# sketch_v1_01.net
KiCad netlist of a schematic drawn in EAGLE
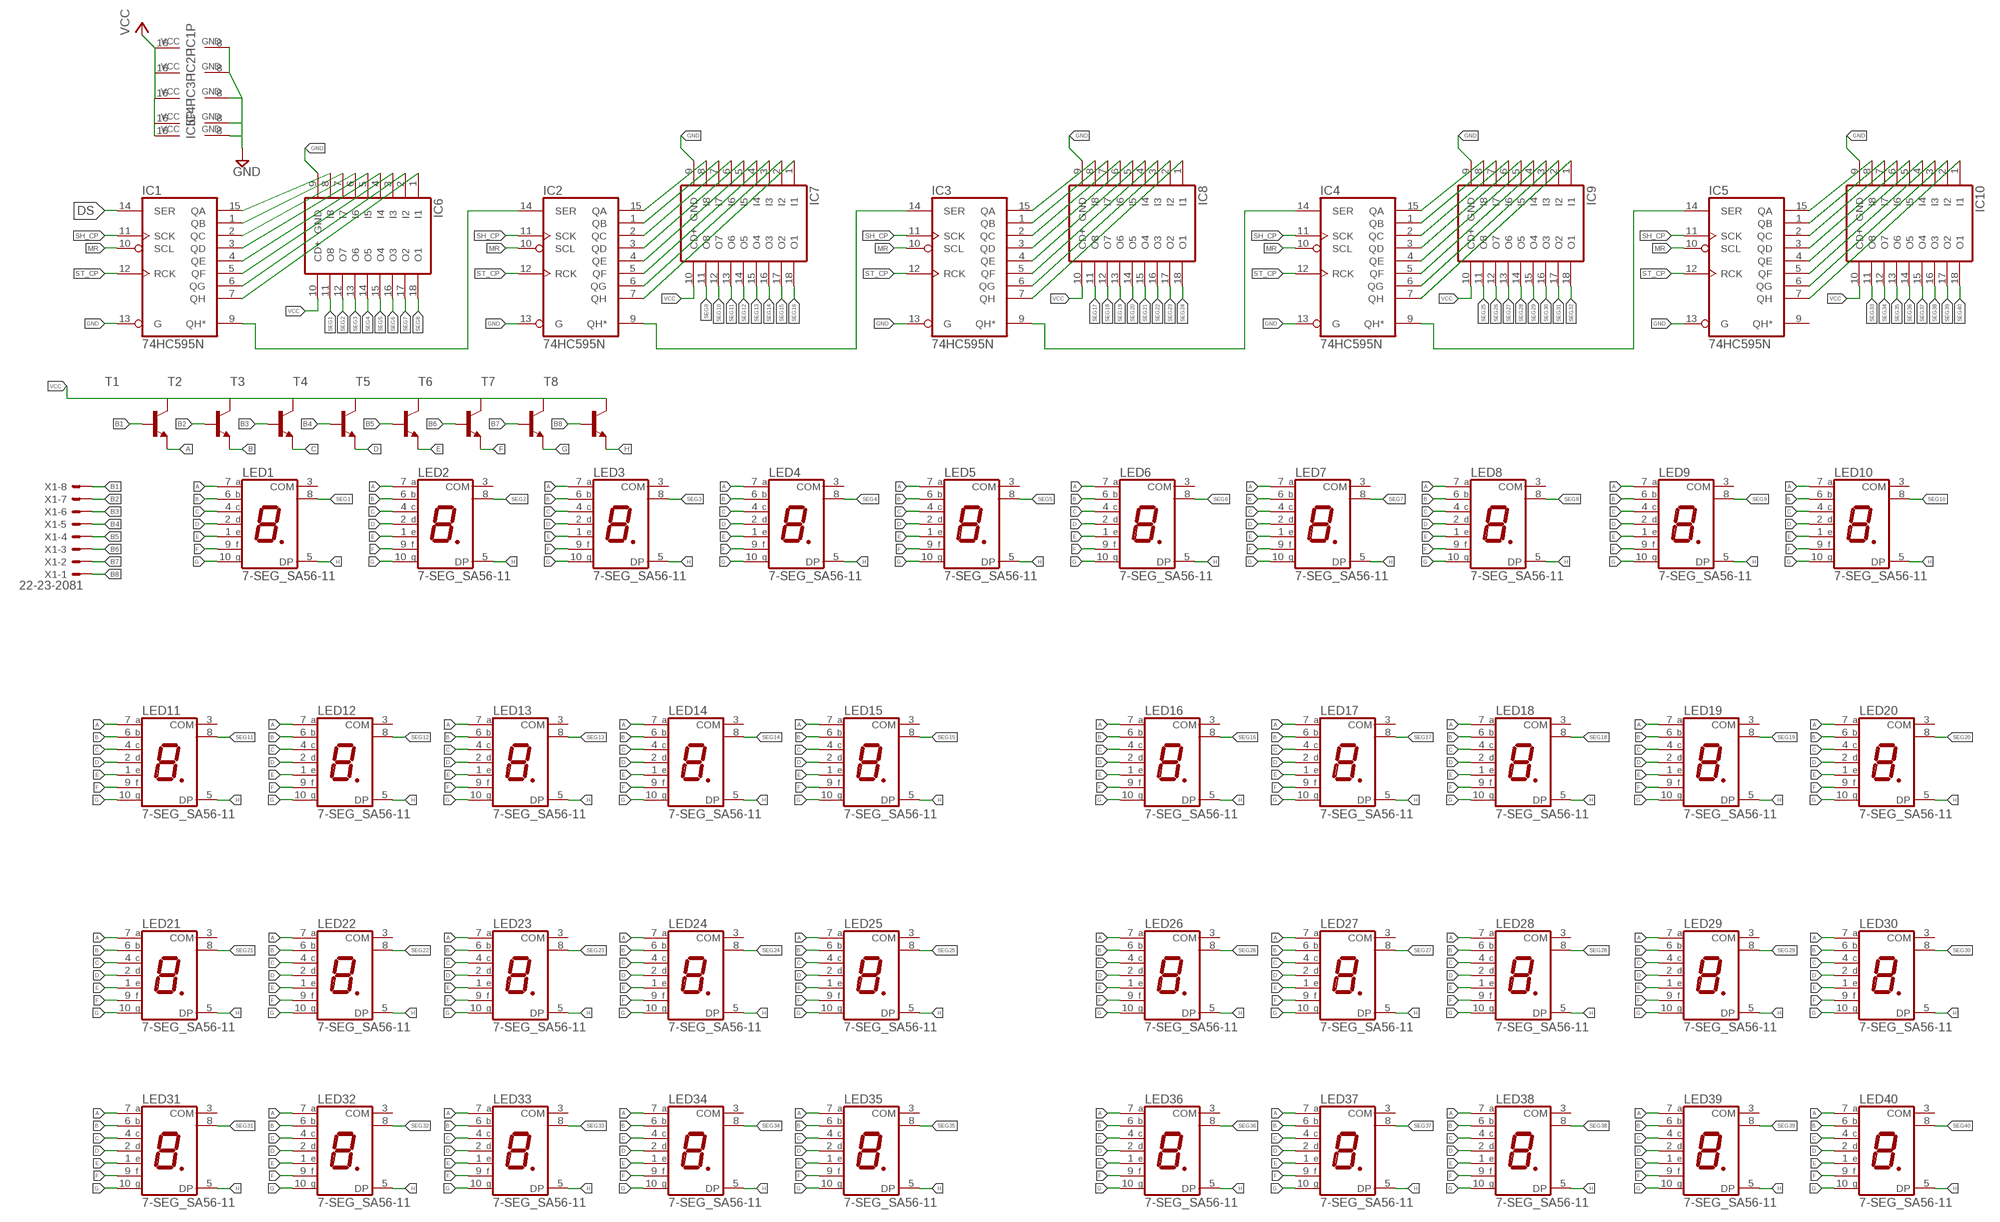
[diagram p0: schematic, sheet 1]

(export (version "E")
  (design (tool "Eeschema 10.0.6"))
  (components
    (comp (ref "IC1")
      (value "74HC595N")
      (footprint "eagle-import:DIL16")
      (libsource (lib "eagle-import") (part "74595NHC"))
    )
    (comp (ref "IC2")
      (value "74HC595N")
      (footprint "eagle-import:DIL16")
      (libsource (lib "eagle-import") (part "74595NHC"))
    )
    (comp (ref "IC3")
      (value "74HC595N")
      (footprint "eagle-import:DIL16")
      (libsource (lib "eagle-import") (part "74595NHC"))
    )
    (comp (ref "IC4")
      (value "74HC595N")
      (footprint "eagle-import:DIL16")
      (libsource (lib "eagle-import") (part "74595NHC"))
    )
    (comp (ref "IC5")
      (value "74HC595N")
      (footprint "eagle-import:DIL16")
      (libsource (lib "eagle-import") (part "74595NHC"))
    )
    (comp (ref "IC6")
      (value "ULN2803A")
      (footprint "eagle-import:DIL18")
      (libsource (lib "eagle-import") (part "ULN2803A"))
    )
    (comp (ref "IC7")
      (value "ULN2803A")
      (footprint "eagle-import:DIL18")
      (libsource (lib "eagle-import") (part "ULN2803A"))
    )
    (comp (ref "IC8")
      (value "ULN2803A")
      (footprint "eagle-import:DIL18")
      (libsource (lib "eagle-import") (part "ULN2803A"))
    )
    (comp (ref "IC9")
      (value "ULN2803A")
      (footprint "eagle-import:DIL18")
      (libsource (lib "eagle-import") (part "ULN2803A"))
    )
    (comp (ref "IC10")
      (value "ULN2803A")
      (footprint "eagle-import:DIL18")
      (libsource (lib "eagle-import") (part "ULN2803A"))
    )
    (comp (ref "LED1")
      (value "7-SEG_SA56-11")
      (footprint "eagle-import:SA56-11")
      (libsource (lib "eagle-import") (part "7-SEG_SA56-11"))
    )
    (comp (ref "LED2")
      (value "7-SEG_SA56-11")
      (footprint "eagle-import:SA56-11")
      (libsource (lib "eagle-import") (part "7-SEG_SA56-11"))
    )
    (comp (ref "LED3")
      (value "7-SEG_SA56-11")
      (footprint "eagle-import:SA56-11")
      (libsource (lib "eagle-import") (part "7-SEG_SA56-11"))
    )
    (comp (ref "LED4")
      (value "7-SEG_SA56-11")
      (footprint "eagle-import:SA56-11")
      (libsource (lib "eagle-import") (part "7-SEG_SA56-11"))
    )
    (comp (ref "LED5")
      (value "7-SEG_SA56-11")
      (footprint "eagle-import:SA56-11")
      (libsource (lib "eagle-import") (part "7-SEG_SA56-11"))
    )
    (comp (ref "LED6")
      (value "7-SEG_SA56-11")
      (footprint "eagle-import:SA56-11")
      (libsource (lib "eagle-import") (part "7-SEG_SA56-11"))
    )
    (comp (ref "LED7")
      (value "7-SEG_SA56-11")
      (footprint "eagle-import:SA56-11")
      (libsource (lib "eagle-import") (part "7-SEG_SA56-11"))
    )
    (comp (ref "LED8")
      (value "7-SEG_SA56-11")
      (footprint "eagle-import:SA56-11")
      (libsource (lib "eagle-import") (part "7-SEG_SA56-11"))
    )
    (comp (ref "LED9")
      (value "7-SEG_SA56-11")
      (footprint "eagle-import:SA56-11")
      (libsource (lib "eagle-import") (part "7-SEG_SA56-11"))
    )
    (comp (ref "LED10")
      (value "7-SEG_SA56-11")
      (footprint "eagle-import:SA56-11")
      (libsource (lib "eagle-import") (part "7-SEG_SA56-11"))
    )
    (comp (ref "LED11")
      (value "7-SEG_SA56-11")
      (footprint "eagle-import:SA56-11")
      (libsource (lib "eagle-import") (part "7-SEG_SA56-11"))
    )
    (comp (ref "LED12")
      (value "7-SEG_SA56-11")
      (footprint "eagle-import:SA56-11")
      (libsource (lib "eagle-import") (part "7-SEG_SA56-11"))
    )
    (comp (ref "LED13")
      (value "7-SEG_SA56-11")
      (footprint "eagle-import:SA56-11")
      (libsource (lib "eagle-import") (part "7-SEG_SA56-11"))
    )
    (comp (ref "LED14")
      (value "7-SEG_SA56-11")
      (footprint "eagle-import:SA56-11")
      (libsource (lib "eagle-import") (part "7-SEG_SA56-11"))
    )
    (comp (ref "LED15")
      (value "7-SEG_SA56-11")
      (footprint "eagle-import:SA56-11")
      (libsource (lib "eagle-import") (part "7-SEG_SA56-11"))
    )
    (comp (ref "LED16")
      (value "7-SEG_SA56-11")
      (footprint "eagle-import:SA56-11")
      (libsource (lib "eagle-import") (part "7-SEG_SA56-11"))
    )
    (comp (ref "LED17")
      (value "7-SEG_SA56-11")
      (footprint "eagle-import:SA56-11")
      (libsource (lib "eagle-import") (part "7-SEG_SA56-11"))
    )
    (comp (ref "LED18")
      (value "7-SEG_SA56-11")
      (footprint "eagle-import:SA56-11")
      (libsource (lib "eagle-import") (part "7-SEG_SA56-11"))
    )
    (comp (ref "LED19")
      (value "7-SEG_SA56-11")
      (footprint "eagle-import:SA56-11")
      (libsource (lib "eagle-import") (part "7-SEG_SA56-11"))
    )
    (comp (ref "LED20")
      (value "7-SEG_SA56-11")
      (footprint "eagle-import:SA56-11")
      (libsource (lib "eagle-import") (part "7-SEG_SA56-11"))
    )
    (comp (ref "LED21")
      (value "7-SEG_SA56-11")
      (footprint "eagle-import:SA56-11")
      (libsource (lib "eagle-import") (part "7-SEG_SA56-11"))
    )
    (comp (ref "LED22")
      (value "7-SEG_SA56-11")
      (footprint "eagle-import:SA56-11")
      (libsource (lib "eagle-import") (part "7-SEG_SA56-11"))
    )
    (comp (ref "LED23")
      (value "7-SEG_SA56-11")
      (footprint "eagle-import:SA56-11")
      (libsource (lib "eagle-import") (part "7-SEG_SA56-11"))
    )
    (comp (ref "LED24")
      (value "7-SEG_SA56-11")
      (footprint "eagle-import:SA56-11")
      (libsource (lib "eagle-import") (part "7-SEG_SA56-11"))
    )
    (comp (ref "LED25")
      (value "7-SEG_SA56-11")
      (footprint "eagle-import:SA56-11")
      (libsource (lib "eagle-import") (part "7-SEG_SA56-11"))
    )
    (comp (ref "LED26")
      (value "7-SEG_SA56-11")
      (footprint "eagle-import:SA56-11")
      (libsource (lib "eagle-import") (part "7-SEG_SA56-11"))
    )
    (comp (ref "LED27")
      (value "7-SEG_SA56-11")
      (footprint "eagle-import:SA56-11")
      (libsource (lib "eagle-import") (part "7-SEG_SA56-11"))
    )
    (comp (ref "LED28")
      (value "7-SEG_SA56-11")
      (footprint "eagle-import:SA56-11")
      (libsource (lib "eagle-import") (part "7-SEG_SA56-11"))
    )
    (comp (ref "LED29")
      (value "7-SEG_SA56-11")
      (footprint "eagle-import:SA56-11")
      (libsource (lib "eagle-import") (part "7-SEG_SA56-11"))
    )
    (comp (ref "LED30")
      (value "7-SEG_SA56-11")
      (footprint "eagle-import:SA56-11")
      (libsource (lib "eagle-import") (part "7-SEG_SA56-11"))
    )
    (comp (ref "LED31")
      (value "7-SEG_SA56-11")
      (footprint "eagle-import:SA56-11")
      (libsource (lib "eagle-import") (part "7-SEG_SA56-11"))
    )
    (comp (ref "LED32")
      (value "7-SEG_SA56-11")
      (footprint "eagle-import:SA56-11")
      (libsource (lib "eagle-import") (part "7-SEG_SA56-11"))
    )
    (comp (ref "LED33")
      (value "7-SEG_SA56-11")
      (footprint "eagle-import:SA56-11")
      (libsource (lib "eagle-import") (part "7-SEG_SA56-11"))
    )
    (comp (ref "LED34")
      (value "7-SEG_SA56-11")
      (footprint "eagle-import:SA56-11")
      (libsource (lib "eagle-import") (part "7-SEG_SA56-11"))
    )
    (comp (ref "LED35")
      (value "7-SEG_SA56-11")
      (footprint "eagle-import:SA56-11")
      (libsource (lib "eagle-import") (part "7-SEG_SA56-11"))
    )
    (comp (ref "LED36")
      (value "7-SEG_SA56-11")
      (footprint "eagle-import:SA56-11")
      (libsource (lib "eagle-import") (part "7-SEG_SA56-11"))
    )
    (comp (ref "LED37")
      (value "7-SEG_SA56-11")
      (footprint "eagle-import:SA56-11")
      (libsource (lib "eagle-import") (part "7-SEG_SA56-11"))
    )
    (comp (ref "LED38")
      (value "7-SEG_SA56-11")
      (footprint "eagle-import:SA56-11")
      (libsource (lib "eagle-import") (part "7-SEG_SA56-11"))
    )
    (comp (ref "LED39")
      (value "7-SEG_SA56-11")
      (footprint "eagle-import:SA56-11")
      (libsource (lib "eagle-import") (part "7-SEG_SA56-11"))
    )
    (comp (ref "LED40")
      (value "7-SEG_SA56-11")
      (footprint "eagle-import:SA56-11")
      (libsource (lib "eagle-import") (part "7-SEG_SA56-11"))
    )
    (comp (ref "T1")
      (value "-NPN-TO92")
      (footprint "eagle-import:TO92")
      (libsource (lib "eagle-import") (part "-NPN-TO92"))
    )
    (comp (ref "T2")
      (value "-NPN-TO92")
      (footprint "eagle-import:TO92")
      (libsource (lib "eagle-import") (part "-NPN-TO92"))
    )
    (comp (ref "T3")
      (value "-NPN-TO92")
      (footprint "eagle-import:TO92")
      (libsource (lib "eagle-import") (part "-NPN-TO92"))
    )
    (comp (ref "T4")
      (value "-NPN-TO92")
      (footprint "eagle-import:TO92")
      (libsource (lib "eagle-import") (part "-NPN-TO92"))
    )
    (comp (ref "T5")
      (value "-NPN-TO92")
      (footprint "eagle-import:TO92")
      (libsource (lib "eagle-import") (part "-NPN-TO92"))
    )
    (comp (ref "T6")
      (value "-NPN-TO92")
      (footprint "eagle-import:TO92")
      (libsource (lib "eagle-import") (part "-NPN-TO92"))
    )
    (comp (ref "T7")
      (value "-NPN-TO92")
      (footprint "eagle-import:TO92")
      (libsource (lib "eagle-import") (part "-NPN-TO92"))
    )
    (comp (ref "T8")
      (value "-NPN-TO92")
      (footprint "eagle-import:TO92")
      (libsource (lib "eagle-import") (part "-NPN-TO92"))
    )
    (comp (ref "X1")
      (value "22-23-2081")
      (footprint "eagle-import:22-23-2081")
      (fields (field (name "MF") "MOLEX"))
      (libsource (lib "eagle-import") (part "22-23-2081"))
    )
  )
  (nets
    (net (code "1") (name "A") (class "Default")
      (node (ref "LED1") (pin "7") (pinfunction "A_7") (pintype "passive"))
      (node (ref "LED10") (pin "7") (pinfunction "A_7") (pintype "passive"))
      (node (ref "LED11") (pin "7") (pinfunction "A_7") (pintype "passive"))
      (node (ref "LED12") (pin "7") (pinfunction "A_7") (pintype "passive"))
      (node (ref "LED13") (pin "7") (pinfunction "A_7") (pintype "passive"))
      (node (ref "LED14") (pin "7") (pinfunction "A_7") (pintype "passive"))
      (node (ref "LED15") (pin "7") (pinfunction "A_7") (pintype "passive"))
      (node (ref "LED16") (pin "7") (pinfunction "A_7") (pintype "passive"))
      (node (ref "LED17") (pin "7") (pinfunction "A_7") (pintype "passive"))
      (node (ref "LED18") (pin "7") (pinfunction "A_7") (pintype "passive"))
      (node (ref "LED19") (pin "7") (pinfunction "A_7") (pintype "passive"))
      (node (ref "LED2") (pin "7") (pinfunction "A_7") (pintype "passive"))
      (node (ref "LED20") (pin "7") (pinfunction "A_7") (pintype "passive"))
      (node (ref "LED21") (pin "7") (pinfunction "A_7") (pintype "passive"))
      (node (ref "LED22") (pin "7") (pinfunction "A_7") (pintype "passive"))
      (node (ref "LED23") (pin "7") (pinfunction "A_7") (pintype "passive"))
      (node (ref "LED24") (pin "7") (pinfunction "A_7") (pintype "passive"))
      (node (ref "LED25") (pin "7") (pinfunction "A_7") (pintype "passive"))
      (node (ref "LED26") (pin "7") (pinfunction "A_7") (pintype "passive"))
      (node (ref "LED27") (pin "7") (pinfunction "A_7") (pintype "passive"))
      (node (ref "LED28") (pin "7") (pinfunction "A_7") (pintype "passive"))
      (node (ref "LED29") (pin "7") (pinfunction "A_7") (pintype "passive"))
      (node (ref "LED3") (pin "7") (pinfunction "A_7") (pintype "passive"))
      (node (ref "LED30") (pin "7") (pinfunction "A_7") (pintype "passive"))
      (node (ref "LED31") (pin "7") (pinfunction "A_7") (pintype "passive"))
      (node (ref "LED32") (pin "7") (pinfunction "A_7") (pintype "passive"))
      (node (ref "LED33") (pin "7") (pinfunction "A_7") (pintype "passive"))
      (node (ref "LED34") (pin "7") (pinfunction "A_7") (pintype "passive"))
      (node (ref "LED35") (pin "7") (pinfunction "A_7") (pintype "passive"))
      (node (ref "LED36") (pin "7") (pinfunction "A_7") (pintype "passive"))
      (node (ref "LED37") (pin "7") (pinfunction "A_7") (pintype "passive"))
      (node (ref "LED38") (pin "7") (pinfunction "A_7") (pintype "passive"))
      (node (ref "LED39") (pin "7") (pinfunction "A_7") (pintype "passive"))
      (node (ref "LED4") (pin "7") (pinfunction "A_7") (pintype "passive"))
      (node (ref "LED40") (pin "7") (pinfunction "A_7") (pintype "passive"))
      (node (ref "LED5") (pin "7") (pinfunction "A_7") (pintype "passive"))
      (node (ref "LED6") (pin "7") (pinfunction "A_7") (pintype "passive"))
      (node (ref "LED7") (pin "7") (pinfunction "A_7") (pintype "passive"))
      (node (ref "LED8") (pin "7") (pinfunction "A_7") (pintype "passive"))
      (node (ref "LED9") (pin "7") (pinfunction "A_7") (pintype "passive"))
      (node (ref "T1") (pin "1") (pinfunction "E_1") (pintype "passive"))
    )
    (net (code "2") (name "B") (class "Default")
      (node (ref "LED1") (pin "6") (pinfunction "B_6") (pintype "passive"))
      (node (ref "LED10") (pin "6") (pinfunction "B_6") (pintype "passive"))
      (node (ref "LED11") (pin "6") (pinfunction "B_6") (pintype "passive"))
      (node (ref "LED12") (pin "6") (pinfunction "B_6") (pintype "passive"))
      (node (ref "LED13") (pin "6") (pinfunction "B_6") (pintype "passive"))
      (node (ref "LED14") (pin "6") (pinfunction "B_6") (pintype "passive"))
      (node (ref "LED15") (pin "6") (pinfunction "B_6") (pintype "passive"))
      (node (ref "LED16") (pin "6") (pinfunction "B_6") (pintype "passive"))
      (node (ref "LED17") (pin "6") (pinfunction "B_6") (pintype "passive"))
      (node (ref "LED18") (pin "6") (pinfunction "B_6") (pintype "passive"))
      (node (ref "LED19") (pin "6") (pinfunction "B_6") (pintype "passive"))
      (node (ref "LED2") (pin "6") (pinfunction "B_6") (pintype "passive"))
      (node (ref "LED20") (pin "6") (pinfunction "B_6") (pintype "passive"))
      (node (ref "LED21") (pin "6") (pinfunction "B_6") (pintype "passive"))
      (node (ref "LED22") (pin "6") (pinfunction "B_6") (pintype "passive"))
      (node (ref "LED23") (pin "6") (pinfunction "B_6") (pintype "passive"))
      (node (ref "LED24") (pin "6") (pinfunction "B_6") (pintype "passive"))
      (node (ref "LED25") (pin "6") (pinfunction "B_6") (pintype "passive"))
      (node (ref "LED26") (pin "6") (pinfunction "B_6") (pintype "passive"))
      (node (ref "LED27") (pin "6") (pinfunction "B_6") (pintype "passive"))
      (node (ref "LED28") (pin "6") (pinfunction "B_6") (pintype "passive"))
      (node (ref "LED29") (pin "6") (pinfunction "B_6") (pintype "passive"))
      (node (ref "LED3") (pin "6") (pinfunction "B_6") (pintype "passive"))
      (node (ref "LED30") (pin "6") (pinfunction "B_6") (pintype "passive"))
      (node (ref "LED31") (pin "6") (pinfunction "B_6") (pintype "passive"))
      (node (ref "LED32") (pin "6") (pinfunction "B_6") (pintype "passive"))
      (node (ref "LED33") (pin "6") (pinfunction "B_6") (pintype "passive"))
      (node (ref "LED34") (pin "6") (pinfunction "B_6") (pintype "passive"))
      (node (ref "LED35") (pin "6") (pinfunction "B_6") (pintype "passive"))
      (node (ref "LED36") (pin "6") (pinfunction "B_6") (pintype "passive"))
      (node (ref "LED37") (pin "6") (pinfunction "B_6") (pintype "passive"))
      (node (ref "LED38") (pin "6") (pinfunction "B_6") (pintype "passive"))
      (node (ref "LED39") (pin "6") (pinfunction "B_6") (pintype "passive"))
      (node (ref "LED4") (pin "6") (pinfunction "B_6") (pintype "passive"))
      (node (ref "LED40") (pin "6") (pinfunction "B_6") (pintype "passive"))
      (node (ref "LED5") (pin "6") (pinfunction "B_6") (pintype "passive"))
      (node (ref "LED6") (pin "6") (pinfunction "B_6") (pintype "passive"))
      (node (ref "LED7") (pin "6") (pinfunction "B_6") (pintype "passive"))
      (node (ref "LED8") (pin "6") (pinfunction "B_6") (pintype "passive"))
      (node (ref "LED9") (pin "6") (pinfunction "B_6") (pintype "passive"))
      (node (ref "T2") (pin "1") (pinfunction "E_1") (pintype "passive"))
    )
    (net (code "3") (name "B1") (class "Default")
      (node (ref "T1") (pin "2") (pinfunction "B_2") (pintype "passive"))
      (node (ref "X1") (pin "8") (pinfunction "S_8") (pintype "passive"))
    )
    (net (code "4") (name "B2") (class "Default")
      (node (ref "T2") (pin "2") (pinfunction "B_2") (pintype "passive"))
      (node (ref "X1") (pin "7") (pinfunction "S_7") (pintype "passive"))
    )
    (net (code "5") (name "B3") (class "Default")
      (node (ref "T3") (pin "2") (pinfunction "B_2") (pintype "passive"))
      (node (ref "X1") (pin "6") (pinfunction "S_6") (pintype "passive"))
    )
    (net (code "6") (name "B4") (class "Default")
      (node (ref "T4") (pin "2") (pinfunction "B_2") (pintype "passive"))
      (node (ref "X1") (pin "5") (pinfunction "S_5") (pintype "passive"))
    )
    (net (code "7") (name "B5") (class "Default")
      (node (ref "T5") (pin "2") (pinfunction "B_2") (pintype "passive"))
      (node (ref "X1") (pin "4") (pinfunction "S_4") (pintype "passive"))
    )
    (net (code "8") (name "B6") (class "Default")
      (node (ref "T6") (pin "2") (pinfunction "B_2") (pintype "passive"))
      (node (ref "X1") (pin "3") (pinfunction "S_3") (pintype "passive"))
    )
    (net (code "9") (name "B7") (class "Default")
      (node (ref "T7") (pin "2") (pinfunction "B_2") (pintype "passive"))
      (node (ref "X1") (pin "2") (pinfunction "S_2") (pintype "passive"))
    )
    (net (code "10") (name "B8") (class "Default")
      (node (ref "T8") (pin "2") (pinfunction "B_2") (pintype "passive"))
      (node (ref "X1") (pin "1") (pinfunction "S_1") (pintype "passive"))
    )
    (net (code "11") (name "C") (class "Default")
      (node (ref "LED1") (pin "4") (pinfunction "C_4") (pintype "passive"))
      (node (ref "LED10") (pin "4") (pinfunction "C_4") (pintype "passive"))
      (node (ref "LED11") (pin "4") (pinfunction "C_4") (pintype "passive"))
      (node (ref "LED12") (pin "4") (pinfunction "C_4") (pintype "passive"))
      (node (ref "LED13") (pin "4") (pinfunction "C_4") (pintype "passive"))
      (node (ref "LED14") (pin "4") (pinfunction "C_4") (pintype "passive"))
      (node (ref "LED15") (pin "4") (pinfunction "C_4") (pintype "passive"))
      (node (ref "LED16") (pin "4") (pinfunction "C_4") (pintype "passive"))
      (node (ref "LED17") (pin "4") (pinfunction "C_4") (pintype "passive"))
      (node (ref "LED18") (pin "4") (pinfunction "C_4") (pintype "passive"))
      (node (ref "LED19") (pin "4") (pinfunction "C_4") (pintype "passive"))
      (node (ref "LED2") (pin "4") (pinfunction "C_4") (pintype "passive"))
      (node (ref "LED20") (pin "4") (pinfunction "C_4") (pintype "passive"))
      (node (ref "LED21") (pin "4") (pinfunction "C_4") (pintype "passive"))
      (node (ref "LED22") (pin "4") (pinfunction "C_4") (pintype "passive"))
      (node (ref "LED23") (pin "4") (pinfunction "C_4") (pintype "passive"))
      (node (ref "LED24") (pin "4") (pinfunction "C_4") (pintype "passive"))
      (node (ref "LED25") (pin "4") (pinfunction "C_4") (pintype "passive"))
      (node (ref "LED26") (pin "4") (pinfunction "C_4") (pintype "passive"))
      (node (ref "LED27") (pin "4") (pinfunction "C_4") (pintype "passive"))
      (node (ref "LED28") (pin "4") (pinfunction "C_4") (pintype "passive"))
      (node (ref "LED29") (pin "4") (pinfunction "C_4") (pintype "passive"))
      (node (ref "LED3") (pin "4") (pinfunction "C_4") (pintype "passive"))
      (node (ref "LED30") (pin "4") (pinfunction "C_4") (pintype "passive"))
      (node (ref "LED31") (pin "4") (pinfunction "C_4") (pintype "passive"))
      (node (ref "LED32") (pin "4") (pinfunction "C_4") (pintype "passive"))
      (node (ref "LED33") (pin "4") (pinfunction "C_4") (pintype "passive"))
      (node (ref "LED34") (pin "4") (pinfunction "C_4") (pintype "passive"))
      (node (ref "LED35") (pin "4") (pinfunction "C_4") (pintype "passive"))
      (node (ref "LED36") (pin "4") (pinfunction "C_4") (pintype "passive"))
      (node (ref "LED37") (pin "4") (pinfunction "C_4") (pintype "passive"))
      (node (ref "LED38") (pin "4") (pinfunction "C_4") (pintype "passive"))
      (node (ref "LED39") (pin "4") (pinfunction "C_4") (pintype "passive"))
      (node (ref "LED4") (pin "4") (pinfunction "C_4") (pintype "passive"))
      (node (ref "LED40") (pin "4") (pinfunction "C_4") (pintype "passive"))
      (node (ref "LED5") (pin "4") (pinfunction "C_4") (pintype "passive"))
      (node (ref "LED6") (pin "4") (pinfunction "C_4") (pintype "passive"))
      (node (ref "LED7") (pin "4") (pinfunction "C_4") (pintype "passive"))
      (node (ref "LED8") (pin "4") (pinfunction "C_4") (pintype "passive"))
      (node (ref "LED9") (pin "4") (pinfunction "C_4") (pintype "passive"))
      (node (ref "T3") (pin "1") (pinfunction "E_1") (pintype "passive"))
    )
    (net (code "12") (name "D") (class "Default")
      (node (ref "LED1") (pin "2") (pinfunction "D_2") (pintype "passive"))
      (node (ref "LED10") (pin "2") (pinfunction "D_2") (pintype "passive"))
      (node (ref "LED11") (pin "2") (pinfunction "D_2") (pintype "passive"))
      (node (ref "LED12") (pin "2") (pinfunction "D_2") (pintype "passive"))
      (node (ref "LED13") (pin "2") (pinfunction "D_2") (pintype "passive"))
      (node (ref "LED14") (pin "2") (pinfunction "D_2") (pintype "passive"))
      (node (ref "LED15") (pin "2") (pinfunction "D_2") (pintype "passive"))
      (node (ref "LED16") (pin "2") (pinfunction "D_2") (pintype "passive"))
      (node (ref "LED17") (pin "2") (pinfunction "D_2") (pintype "passive"))
      (node (ref "LED18") (pin "2") (pinfunction "D_2") (pintype "passive"))
      (node (ref "LED19") (pin "2") (pinfunction "D_2") (pintype "passive"))
      (node (ref "LED2") (pin "2") (pinfunction "D_2") (pintype "passive"))
      (node (ref "LED20") (pin "2") (pinfunction "D_2") (pintype "passive"))
      (node (ref "LED21") (pin "2") (pinfunction "D_2") (pintype "passive"))
      (node (ref "LED22") (pin "2") (pinfunction "D_2") (pintype "passive"))
      (node (ref "LED23") (pin "2") (pinfunction "D_2") (pintype "passive"))
      (node (ref "LED24") (pin "2") (pinfunction "D_2") (pintype "passive"))
      (node (ref "LED25") (pin "2") (pinfunction "D_2") (pintype "passive"))
      (node (ref "LED26") (pin "2") (pinfunction "D_2") (pintype "passive"))
      (node (ref "LED27") (pin "2") (pinfunction "D_2") (pintype "passive"))
      (node (ref "LED28") (pin "2") (pinfunction "D_2") (pintype "passive"))
      (node (ref "LED29") (pin "2") (pinfunction "D_2") (pintype "passive"))
      (node (ref "LED3") (pin "2") (pinfunction "D_2") (pintype "passive"))
      (node (ref "LED30") (pin "2") (pinfunction "D_2") (pintype "passive"))
      (node (ref "LED31") (pin "2") (pinfunction "D_2") (pintype "passive"))
      (node (ref "LED32") (pin "2") (pinfunction "D_2") (pintype "passive"))
      (node (ref "LED33") (pin "2") (pinfunction "D_2") (pintype "passive"))
      (node (ref "LED34") (pin "2") (pinfunction "D_2") (pintype "passive"))
      (node (ref "LED35") (pin "2") (pinfunction "D_2") (pintype "passive"))
      (node (ref "LED36") (pin "2") (pinfunction "D_2") (pintype "passive"))
      (node (ref "LED37") (pin "2") (pinfunction "D_2") (pintype "passive"))
      (node (ref "LED38") (pin "2") (pinfunction "D_2") (pintype "passive"))
      (node (ref "LED39") (pin "2") (pinfunction "D_2") (pintype "passive"))
      (node (ref "LED4") (pin "2") (pinfunction "D_2") (pintype "passive"))
      (node (ref "LED40") (pin "2") (pinfunction "D_2") (pintype "passive"))
      (node (ref "LED5") (pin "2") (pinfunction "D_2") (pintype "passive"))
      (node (ref "LED6") (pin "2") (pinfunction "D_2") (pintype "passive"))
      (node (ref "LED7") (pin "2") (pinfunction "D_2") (pintype "passive"))
      (node (ref "LED8") (pin "2") (pinfunction "D_2") (pintype "passive"))
      (node (ref "LED9") (pin "2") (pinfunction "D_2") (pintype "passive"))
      (node (ref "T4") (pin "1") (pinfunction "E_1") (pintype "passive"))
    )
    (net (code "13") (name "DS") (class "Default")
      (node (ref "IC1") (pin "14") (pinfunction "SER_14") (pintype "input"))
    )
    (net (code "14") (name "E") (class "Default")
      (node (ref "LED1") (pin "1") (pinfunction "E_1") (pintype "passive"))
      (node (ref "LED10") (pin "1") (pinfunction "E_1") (pintype "passive"))
      (node (ref "LED11") (pin "1") (pinfunction "E_1") (pintype "passive"))
      (node (ref "LED12") (pin "1") (pinfunction "E_1") (pintype "passive"))
      (node (ref "LED13") (pin "1") (pinfunction "E_1") (pintype "passive"))
      (node (ref "LED14") (pin "1") (pinfunction "E_1") (pintype "passive"))
      (node (ref "LED15") (pin "1") (pinfunction "E_1") (pintype "passive"))
      (node (ref "LED16") (pin "1") (pinfunction "E_1") (pintype "passive"))
      (node (ref "LED17") (pin "1") (pinfunction "E_1") (pintype "passive"))
      (node (ref "LED18") (pin "1") (pinfunction "E_1") (pintype "passive"))
      (node (ref "LED19") (pin "1") (pinfunction "E_1") (pintype "passive"))
      (node (ref "LED2") (pin "1") (pinfunction "E_1") (pintype "passive"))
      (node (ref "LED20") (pin "1") (pinfunction "E_1") (pintype "passive"))
      (node (ref "LED21") (pin "1") (pinfunction "E_1") (pintype "passive"))
      (node (ref "LED22") (pin "1") (pinfunction "E_1") (pintype "passive"))
      (node (ref "LED23") (pin "1") (pinfunction "E_1") (pintype "passive"))
      (node (ref "LED24") (pin "1") (pinfunction "E_1") (pintype "passive"))
      (node (ref "LED25") (pin "1") (pinfunction "E_1") (pintype "passive"))
      (node (ref "LED26") (pin "1") (pinfunction "E_1") (pintype "passive"))
      (node (ref "LED27") (pin "1") (pinfunction "E_1") (pintype "passive"))
      (node (ref "LED28") (pin "1") (pinfunction "E_1") (pintype "passive"))
      (node (ref "LED29") (pin "1") (pinfunction "E_1") (pintype "passive"))
      (node (ref "LED3") (pin "1") (pinfunction "E_1") (pintype "passive"))
      (node (ref "LED30") (pin "1") (pinfunction "E_1") (pintype "passive"))
      (node (ref "LED31") (pin "1") (pinfunction "E_1") (pintype "passive"))
      (node (ref "LED32") (pin "1") (pinfunction "E_1") (pintype "passive"))
      (node (ref "LED33") (pin "1") (pinfunction "E_1") (pintype "passive"))
      (node (ref "LED34") (pin "1") (pinfunction "E_1") (pintype "passive"))
      (node (ref "LED35") (pin "1") (pinfunction "E_1") (pintype "passive"))
      (node (ref "LED36") (pin "1") (pinfunction "E_1") (pintype "passive"))
      (node (ref "LED37") (pin "1") (pinfunction "E_1") (pintype "passive"))
      (node (ref "LED38") (pin "1") (pinfunction "E_1") (pintype "passive"))
      (node (ref "LED39") (pin "1") (pinfunction "E_1") (pintype "passive"))
      (node (ref "LED4") (pin "1") (pinfunction "E_1") (pintype "passive"))
      (node (ref "LED40") (pin "1") (pinfunction "E_1") (pintype "passive"))
      (node (ref "LED5") (pin "1") (pinfunction "E_1") (pintype "passive"))
      (node (ref "LED6") (pin "1") (pinfunction "E_1") (pintype "passive"))
      (node (ref "LED7") (pin "1") (pinfunction "E_1") (pintype "passive"))
      (node (ref "LED8") (pin "1") (pinfunction "E_1") (pintype "passive"))
      (node (ref "LED9") (pin "1") (pinfunction "E_1") (pintype "passive"))
      (node (ref "T5") (pin "1") (pinfunction "E_1") (pintype "passive"))
    )
    (net (code "15") (name "F") (class "Default")
      (node (ref "LED1") (pin "9") (pinfunction "F_9") (pintype "passive"))
      (node (ref "LED10") (pin "9") (pinfunction "F_9") (pintype "passive"))
      (node (ref "LED11") (pin "9") (pinfunction "F_9") (pintype "passive"))
      (node (ref "LED12") (pin "9") (pinfunction "F_9") (pintype "passive"))
      (node (ref "LED13") (pin "9") (pinfunction "F_9") (pintype "passive"))
      (node (ref "LED14") (pin "9") (pinfunction "F_9") (pintype "passive"))
      (node (ref "LED15") (pin "9") (pinfunction "F_9") (pintype "passive"))
      (node (ref "LED16") (pin "9") (pinfunction "F_9") (pintype "passive"))
      (node (ref "LED17") (pin "9") (pinfunction "F_9") (pintype "passive"))
      (node (ref "LED18") (pin "9") (pinfunction "F_9") (pintype "passive"))
      (node (ref "LED19") (pin "9") (pinfunction "F_9") (pintype "passive"))
      (node (ref "LED2") (pin "9") (pinfunction "F_9") (pintype "passive"))
      (node (ref "LED20") (pin "9") (pinfunction "F_9") (pintype "passive"))
      (node (ref "LED21") (pin "9") (pinfunction "F_9") (pintype "passive"))
      (node (ref "LED22") (pin "9") (pinfunction "F_9") (pintype "passive"))
      (node (ref "LED23") (pin "9") (pinfunction "F_9") (pintype "passive"))
      (node (ref "LED24") (pin "9") (pinfunction "F_9") (pintype "passive"))
      (node (ref "LED25") (pin "9") (pinfunction "F_9") (pintype "passive"))
      (node (ref "LED26") (pin "9") (pinfunction "F_9") (pintype "passive"))
      (node (ref "LED27") (pin "9") (pinfunction "F_9") (pintype "passive"))
      (node (ref "LED28") (pin "9") (pinfunction "F_9") (pintype "passive"))
      (node (ref "LED29") (pin "9") (pinfunction "F_9") (pintype "passive"))
      (node (ref "LED3") (pin "9") (pinfunction "F_9") (pintype "passive"))
      (node (ref "LED30") (pin "9") (pinfunction "F_9") (pintype "passive"))
      (node (ref "LED31") (pin "9") (pinfunction "F_9") (pintype "passive"))
      (node (ref "LED32") (pin "9") (pinfunction "F_9") (pintype "passive"))
      (node (ref "LED33") (pin "9") (pinfunction "F_9") (pintype "passive"))
      (node (ref "LED34") (pin "9") (pinfunction "F_9") (pintype "passive"))
      (node (ref "LED35") (pin "9") (pinfunction "F_9") (pintype "passive"))
      (node (ref "LED36") (pin "9") (pinfunction "F_9") (pintype "passive"))
      (node (ref "LED37") (pin "9") (pinfunction "F_9") (pintype "passive"))
      (node (ref "LED38") (pin "9") (pinfunction "F_9") (pintype "passive"))
      (node (ref "LED39") (pin "9") (pinfunction "F_9") (pintype "passive"))
      (node (ref "LED4") (pin "9") (pinfunction "F_9") (pintype "passive"))
      (node (ref "LED40") (pin "9") (pinfunction "F_9") (pintype "passive"))
      (node (ref "LED5") (pin "9") (pinfunction "F_9") (pintype "passive"))
      (node (ref "LED6") (pin "9") (pinfunction "F_9") (pintype "passive"))
      (node (ref "LED7") (pin "9") (pinfunction "F_9") (pintype "passive"))
      (node (ref "LED8") (pin "9") (pinfunction "F_9") (pintype "passive"))
      (node (ref "LED9") (pin "9") (pinfunction "F_9") (pintype "passive"))
      (node (ref "T6") (pin "1") (pinfunction "E_1") (pintype "passive"))
    )
    (net (code "16") (name "G") (class "Default")
      (node (ref "LED1") (pin "10") (pinfunction "G_10") (pintype "passive"))
      (node (ref "LED10") (pin "10") (pinfunction "G_10") (pintype "passive"))
      (node (ref "LED11") (pin "10") (pinfunction "G_10") (pintype "passive"))
      (node (ref "LED12") (pin "10") (pinfunction "G_10") (pintype "passive"))
      (node (ref "LED13") (pin "10") (pinfunction "G_10") (pintype "passive"))
      (node (ref "LED14") (pin "10") (pinfunction "G_10") (pintype "passive"))
      (node (ref "LED15") (pin "10") (pinfunction "G_10") (pintype "passive"))
      (node (ref "LED16") (pin "10") (pinfunction "G_10") (pintype "passive"))
      (node (ref "LED17") (pin "10") (pinfunction "G_10") (pintype "passive"))
      (node (ref "LED18") (pin "10") (pinfunction "G_10") (pintype "passive"))
      (node (ref "LED19") (pin "10") (pinfunction "G_10") (pintype "passive"))
      (node (ref "LED2") (pin "10") (pinfunction "G_10") (pintype "passive"))
      (node (ref "LED20") (pin "10") (pinfunction "G_10") (pintype "passive"))
      (node (ref "LED21") (pin "10") (pinfunction "G_10") (pintype "passive"))
      (node (ref "LED22") (pin "10") (pinfunction "G_10") (pintype "passive"))
      (node (ref "LED23") (pin "10") (pinfunction "G_10") (pintype "passive"))
      (node (ref "LED24") (pin "10") (pinfunction "G_10") (pintype "passive"))
      (node (ref "LED25") (pin "10") (pinfunction "G_10") (pintype "passive"))
      (node (ref "LED26") (pin "10") (pinfunction "G_10") (pintype "passive"))
      (node (ref "LED27") (pin "10") (pinfunction "G_10") (pintype "passive"))
      (node (ref "LED28") (pin "10") (pinfunction "G_10") (pintype "passive"))
      (node (ref "LED29") (pin "10") (pinfunction "G_10") (pintype "passive"))
      (node (ref "LED3") (pin "10") (pinfunction "G_10") (pintype "passive"))
      (node (ref "LED30") (pin "10") (pinfunction "G_10") (pintype "passive"))
      (node (ref "LED31") (pin "10") (pinfunction "G_10") (pintype "passive"))
      (node (ref "LED32") (pin "10") (pinfunction "G_10") (pintype "passive"))
      (node (ref "LED33") (pin "10") (pinfunction "G_10") (pintype "passive"))
      (node (ref "LED34") (pin "10") (pinfunction "G_10") (pintype "passive"))
      (node (ref "LED35") (pin "10") (pinfunction "G_10") (pintype "passive"))
      (node (ref "LED36") (pin "10") (pinfunction "G_10") (pintype "passive"))
      (node (ref "LED37") (pin "10") (pinfunction "G_10") (pintype "passive"))
      (node (ref "LED38") (pin "10") (pinfunction "G_10") (pintype "passive"))
      (node (ref "LED39") (pin "10") (pinfunction "G_10") (pintype "passive"))
      (node (ref "LED4") (pin "10") (pinfunction "G_10") (pintype "passive"))
      (node (ref "LED40") (pin "10") (pinfunction "G_10") (pintype "passive"))
      (node (ref "LED5") (pin "10") (pinfunction "G_10") (pintype "passive"))
      (node (ref "LED6") (pin "10") (pinfunction "G_10") (pintype "passive"))
      (node (ref "LED7") (pin "10") (pinfunction "G_10") (pintype "passive"))
      (node (ref "LED8") (pin "10") (pinfunction "G_10") (pintype "passive"))
      (node (ref "LED9") (pin "10") (pinfunction "G_10") (pintype "passive"))
      (node (ref "T7") (pin "1") (pinfunction "E_1") (pintype "passive"))
    )
    (net (code "17") (name "GND") (class "Default")
      (node (ref "IC1") (pin "13") (pinfunction "G_13") (pintype "input"))
      (node (ref "IC1") (pin "8") (pinfunction "GND_8") (pintype "power_in"))
      (node (ref "IC10") (pin "9") (pinfunction "GND_9") (pintype "power_in"))
      (node (ref "IC2") (pin "13") (pinfunction "G_13") (pintype "input"))
      (node (ref "IC2") (pin "8") (pinfunction "GND_8") (pintype "power_in"))
      (node (ref "IC3") (pin "13") (pinfunction "G_13") (pintype "input"))
      (node (ref "IC3") (pin "8") (pinfunction "GND_8") (pintype "power_in"))
      (node (ref "IC4") (pin "13") (pinfunction "G_13") (pintype "input"))
      (node (ref "IC4") (pin "8") (pinfunction "GND_8") (pintype "power_in"))
      (node (ref "IC5") (pin "13") (pinfunction "G_13") (pintype "input"))
      (node (ref "IC5") (pin "8") (pinfunction "GND_8") (pintype "power_in"))
      (node (ref "IC6") (pin "9") (pinfunction "GND_9") (pintype "power_in"))
      (node (ref "IC7") (pin "9") (pinfunction "GND_9") (pintype "power_in"))
      (node (ref "IC8") (pin "9") (pinfunction "GND_9") (pintype "power_in"))
      (node (ref "IC9") (pin "9") (pinfunction "GND_9") (pintype "power_in"))
    )
    (net (code "18") (name "H") (class "Default")
      (node (ref "LED1") (pin "5") (pinfunction "DP_5") (pintype "passive"))
      (node (ref "LED10") (pin "5") (pinfunction "DP_5") (pintype "passive"))
      (node (ref "LED11") (pin "5") (pinfunction "DP_5") (pintype "passive"))
      (node (ref "LED12") (pin "5") (pinfunction "DP_5") (pintype "passive"))
      (node (ref "LED13") (pin "5") (pinfunction "DP_5") (pintype "passive"))
      (node (ref "LED14") (pin "5") (pinfunction "DP_5") (pintype "passive"))
      (node (ref "LED15") (pin "5") (pinfunction "DP_5") (pintype "passive"))
      (node (ref "LED16") (pin "5") (pinfunction "DP_5") (pintype "passive"))
      (node (ref "LED17") (pin "5") (pinfunction "DP_5") (pintype "passive"))
      (node (ref "LED18") (pin "5") (pinfunction "DP_5") (pintype "passive"))
      (node (ref "LED19") (pin "5") (pinfunction "DP_5") (pintype "passive"))
      (node (ref "LED2") (pin "5") (pinfunction "DP_5") (pintype "passive"))
      (node (ref "LED20") (pin "5") (pinfunction "DP_5") (pintype "passive"))
      (node (ref "LED21") (pin "5") (pinfunction "DP_5") (pintype "passive"))
      (node (ref "LED22") (pin "5") (pinfunction "DP_5") (pintype "passive"))
      (node (ref "LED23") (pin "5") (pinfunction "DP_5") (pintype "passive"))
      (node (ref "LED24") (pin "5") (pinfunction "DP_5") (pintype "passive"))
      (node (ref "LED25") (pin "5") (pinfunction "DP_5") (pintype "passive"))
      (node (ref "LED26") (pin "5") (pinfunction "DP_5") (pintype "passive"))
      (node (ref "LED27") (pin "5") (pinfunction "DP_5") (pintype "passive"))
      (node (ref "LED28") (pin "5") (pinfunction "DP_5") (pintype "passive"))
      (node (ref "LED29") (pin "5") (pinfunction "DP_5") (pintype "passive"))
      (node (ref "LED3") (pin "5") (pinfunction "DP_5") (pintype "passive"))
      (node (ref "LED30") (pin "5") (pinfunction "DP_5") (pintype "passive"))
      (node (ref "LED31") (pin "5") (pinfunction "DP_5") (pintype "passive"))
      (node (ref "LED32") (pin "5") (pinfunction "DP_5") (pintype "passive"))
      (node (ref "LED33") (pin "5") (pinfunction "DP_5") (pintype "passive"))
      (node (ref "LED34") (pin "5") (pinfunction "DP_5") (pintype "passive"))
      (node (ref "LED35") (pin "5") (pinfunction "DP_5") (pintype "passive"))
      (node (ref "LED36") (pin "5") (pinfunction "DP_5") (pintype "passive"))
      (node (ref "LED37") (pin "5") (pinfunction "DP_5") (pintype "passive"))
      (node (ref "LED38") (pin "5") (pinfunction "DP_5") (pintype "passive"))
      (node (ref "LED39") (pin "5") (pinfunction "DP_5") (pintype "passive"))
      (node (ref "LED4") (pin "5") (pinfunction "DP_5") (pintype "passive"))
      (node (ref "LED40") (pin "5") (pinfunction "DP_5") (pintype "passive"))
      (node (ref "LED5") (pin "5") (pinfunction "DP_5") (pintype "passive"))
      (node (ref "LED6") (pin "5") (pinfunction "DP_5") (pintype "passive"))
      (node (ref "LED7") (pin "5") (pinfunction "DP_5") (pintype "passive"))
      (node (ref "LED8") (pin "5") (pinfunction "DP_5") (pintype "passive"))
      (node (ref "LED9") (pin "5") (pinfunction "DP_5") (pintype "passive"))
      (node (ref "T8") (pin "1") (pinfunction "E_1") (pintype "passive"))
    )
    (net (code "19") (name "MR") (class "Default")
      (node (ref "IC1") (pin "10") (pinfunction "SCL_10") (pintype "input"))
      (node (ref "IC2") (pin "10") (pinfunction "SCL_10") (pintype "input"))
      (node (ref "IC3") (pin "10") (pinfunction "SCL_10") (pintype "input"))
      (node (ref "IC4") (pin "10") (pinfunction "SCL_10") (pintype "input"))
      (node (ref "IC5") (pin "10") (pinfunction "SCL_10") (pintype "input"))
    )
    (net (code "20") (name "Net-(IC1A-QA)") (class "Default")
      (node (ref "IC1") (pin "15") (pinfunction "QA_15") (pintype "tri_state"))
      (node (ref "IC6") (pin "8") (pinfunction "I8_8") (pintype "input"))
    )
    (net (code "21") (name "Net-(IC1A-QB)") (class "Default")
      (node (ref "IC1") (pin "1") (pinfunction "QB_1") (pintype "tri_state"))
      (node (ref "IC6") (pin "7") (pinfunction "I7_7") (pintype "input"))
    )
    (net (code "22") (name "Net-(IC1A-QC)") (class "Default")
      (node (ref "IC1") (pin "2") (pinfunction "QC_2") (pintype "tri_state"))
      (node (ref "IC6") (pin "6") (pinfunction "I6_6") (pintype "input"))
    )
    (net (code "23") (name "Net-(IC1A-QD)") (class "Default")
      (node (ref "IC1") (pin "3") (pinfunction "QD_3") (pintype "tri_state"))
      (node (ref "IC6") (pin "5") (pinfunction "I5_5") (pintype "input"))
    )
    (net (code "24") (name "Net-(IC1A-QE)") (class "Default")
      (node (ref "IC1") (pin "4") (pinfunction "QE_4") (pintype "tri_state"))
      (node (ref "IC6") (pin "4") (pinfunction "I4_4") (pintype "input"))
    )
    (net (code "25") (name "Net-(IC1A-QF)") (class "Default")
      (node (ref "IC1") (pin "5") (pinfunction "QF_5") (pintype "tri_state"))
      (node (ref "IC6") (pin "3") (pinfunction "I3_3") (pintype "input"))
    )
    (net (code "26") (name "Net-(IC1A-QG)") (class "Default")
      (node (ref "IC1") (pin "6") (pinfunction "QG_6") (pintype "tri_state"))
      (node (ref "IC6") (pin "2") (pinfunction "I2_2") (pintype "input"))
    )
    (net (code "27") (name "Net-(IC1A-QH)") (class "Default")
      (node (ref "IC1") (pin "7") (pinfunction "QH_7") (pintype "tri_state"))
      (node (ref "IC6") (pin "1") (pinfunction "I1_1") (pintype "input"))
    )
    (net (code "28") (name "Net-(IC1A-QH*)") (class "Default")
      (node (ref "IC1") (pin "9") (pinfunction "QH*_9") (pintype "tri_state"))
      (node (ref "IC2") (pin "14") (pinfunction "SER_14") (pintype "input"))
    )
    (net (code "29") (name "Net-(IC2A-QA)") (class "Default")
      (node (ref "IC2") (pin "15") (pinfunction "QA_15") (pintype "tri_state"))
      (node (ref "IC7") (pin "8") (pinfunction "I8_8") (pintype "input"))
    )
    (net (code "30") (name "Net-(IC2A-QB)") (class "Default")
      (node (ref "IC2") (pin "1") (pinfunction "QB_1") (pintype "tri_state"))
      (node (ref "IC7") (pin "7") (pinfunction "I7_7") (pintype "input"))
    )
    (net (code "31") (name "Net-(IC2A-QC)") (class "Default")
      (node (ref "IC2") (pin "2") (pinfunction "QC_2") (pintype "tri_state"))
      (node (ref "IC7") (pin "6") (pinfunction "I6_6") (pintype "input"))
    )
    (net (code "32") (name "Net-(IC2A-QD)") (class "Default")
      (node (ref "IC2") (pin "3") (pinfunction "QD_3") (pintype "tri_state"))
      (node (ref "IC7") (pin "5") (pinfunction "I5_5") (pintype "input"))
    )
    (net (code "33") (name "Net-(IC2A-QE)") (class "Default")
      (node (ref "IC2") (pin "4") (pinfunction "QE_4") (pintype "tri_state"))
      (node (ref "IC7") (pin "4") (pinfunction "I4_4") (pintype "input"))
    )
    (net (code "34") (name "Net-(IC2A-QF)") (class "Default")
      (node (ref "IC2") (pin "5") (pinfunction "QF_5") (pintype "tri_state"))
      (node (ref "IC7") (pin "3") (pinfunction "I3_3") (pintype "input"))
    )
    (net (code "35") (name "Net-(IC2A-QG)") (class "Default")
      (node (ref "IC2") (pin "6") (pinfunction "QG_6") (pintype "tri_state"))
      (node (ref "IC7") (pin "2") (pinfunction "I2_2") (pintype "input"))
    )
    (net (code "36") (name "Net-(IC2A-QH)") (class "Default")
      (node (ref "IC2") (pin "7") (pinfunction "QH_7") (pintype "tri_state"))
      (node (ref "IC7") (pin "1") (pinfunction "I1_1") (pintype "input"))
    )
    (net (code "37") (name "Net-(IC2A-QH*)") (class "Default")
      (node (ref "IC2") (pin "9") (pinfunction "QH*_9") (pintype "tri_state"))
      (node (ref "IC3") (pin "14") (pinfunction "SER_14") (pintype "input"))
    )
    (net (code "38") (name "Net-(IC3A-QA)") (class "Default")
      (node (ref "IC3") (pin "15") (pinfunction "QA_15") (pintype "tri_state"))
      (node (ref "IC8") (pin "8") (pinfunction "I8_8") (pintype "input"))
    )
    (net (code "39") (name "Net-(IC3A-QB)") (class "Default")
      (node (ref "IC3") (pin "1") (pinfunction "QB_1") (pintype "tri_state"))
      (node (ref "IC8") (pin "7") (pinfunction "I7_7") (pintype "input"))
    )
    (net (code "40") (name "Net-(IC3A-QC)") (class "Default")
      (node (ref "IC3") (pin "2") (pinfunction "QC_2") (pintype "tri_state"))
      (node (ref "IC8") (pin "6") (pinfunction "I6_6") (pintype "input"))
    )
    (net (code "41") (name "Net-(IC3A-QD)") (class "Default")
      (node (ref "IC3") (pin "3") (pinfunction "QD_3") (pintype "tri_state"))
      (node (ref "IC8") (pin "5") (pinfunction "I5_5") (pintype "input"))
    )
    (net (code "42") (name "Net-(IC3A-QE)") (class "Default")
      (node (ref "IC3") (pin "4") (pinfunction "QE_4") (pintype "tri_state"))
      (node (ref "IC8") (pin "4") (pinfunction "I4_4") (pintype "input"))
    )
    (net (code "43") (name "Net-(IC3A-QF)") (class "Default")
      (node (ref "IC3") (pin "5") (pinfunction "QF_5") (pintype "tri_state"))
      (node (ref "IC8") (pin "3") (pinfunction "I3_3") (pintype "input"))
    )
    (net (code "44") (name "Net-(IC3A-QG)") (class "Default")
      (node (ref "IC3") (pin "6") (pinfunction "QG_6") (pintype "tri_state"))
      (node (ref "IC8") (pin "2") (pinfunction "I2_2") (pintype "input"))
    )
    (net (code "45") (name "Net-(IC3A-QH)") (class "Default")
      (node (ref "IC3") (pin "7") (pinfunction "QH_7") (pintype "tri_state"))
      (node (ref "IC8") (pin "1") (pinfunction "I1_1") (pintype "input"))
    )
    (net (code "46") (name "Net-(IC3A-QH*)") (class "Default")
      (node (ref "IC3") (pin "9") (pinfunction "QH*_9") (pintype "tri_state"))
      (node (ref "IC4") (pin "14") (pinfunction "SER_14") (pintype "input"))
    )
    (net (code "47") (name "Net-(IC4A-QA)") (class "Default")
      (node (ref "IC4") (pin "15") (pinfunction "QA_15") (pintype "tri_state"))
      (node (ref "IC9") (pin "8") (pinfunction "I8_8") (pintype "input"))
    )
    (net (code "48") (name "Net-(IC4A-QB)") (class "Default")
      (node (ref "IC4") (pin "1") (pinfunction "QB_1") (pintype "tri_state"))
      (node (ref "IC9") (pin "7") (pinfunction "I7_7") (pintype "input"))
    )
    (net (code "49") (name "Net-(IC4A-QC)") (class "Default")
      (node (ref "IC4") (pin "2") (pinfunction "QC_2") (pintype "tri_state"))
      (node (ref "IC9") (pin "6") (pinfunction "I6_6") (pintype "input"))
    )
    (net (code "50") (name "Net-(IC4A-QD)") (class "Default")
      (node (ref "IC4") (pin "3") (pinfunction "QD_3") (pintype "tri_state"))
      (node (ref "IC9") (pin "5") (pinfunction "I5_5") (pintype "input"))
    )
    (net (code "51") (name "Net-(IC4A-QE)") (class "Default")
      (node (ref "IC4") (pin "4") (pinfunction "QE_4") (pintype "tri_state"))
      (node (ref "IC9") (pin "4") (pinfunction "I4_4") (pintype "input"))
    )
    (net (code "52") (name "Net-(IC4A-QF)") (class "Default")
      (node (ref "IC4") (pin "5") (pinfunction "QF_5") (pintype "tri_state"))
      (node (ref "IC9") (pin "3") (pinfunction "I3_3") (pintype "input"))
    )
    (net (code "53") (name "Net-(IC4A-QG)") (class "Default")
      (node (ref "IC4") (pin "6") (pinfunction "QG_6") (pintype "tri_state"))
      (node (ref "IC9") (pin "2") (pinfunction "I2_2") (pintype "input"))
    )
    (net (code "54") (name "Net-(IC4A-QH)") (class "Default")
      (node (ref "IC4") (pin "7") (pinfunction "QH_7") (pintype "tri_state"))
      (node (ref "IC9") (pin "1") (pinfunction "I1_1") (pintype "input"))
    )
    (net (code "55") (name "Net-(IC4A-QH*)") (class "Default")
      (node (ref "IC4") (pin "9") (pinfunction "QH*_9") (pintype "tri_state"))
      (node (ref "IC5") (pin "14") (pinfunction "SER_14") (pintype "input"))
    )
    (net (code "56") (name "Net-(IC10-I1)") (class "Default")
      (node (ref "IC10") (pin "1") (pinfunction "I1_1") (pintype "input"))
      (node (ref "IC5") (pin "7") (pinfunction "QH_7") (pintype "tri_state"))
    )
    (net (code "57") (name "Net-(IC10-I2)") (class "Default")
      (node (ref "IC10") (pin "2") (pinfunction "I2_2") (pintype "input"))
      (node (ref "IC5") (pin "6") (pinfunction "QG_6") (pintype "tri_state"))
    )
    (net (code "58") (name "Net-(IC10-I3)") (class "Default")
      (node (ref "IC10") (pin "3") (pinfunction "I3_3") (pintype "input"))
      (node (ref "IC5") (pin "5") (pinfunction "QF_5") (pintype "tri_state"))
    )
    (net (code "59") (name "Net-(IC10-I4)") (class "Default")
      (node (ref "IC10") (pin "4") (pinfunction "I4_4") (pintype "input"))
      (node (ref "IC5") (pin "4") (pinfunction "QE_4") (pintype "tri_state"))
    )
    (net (code "60") (name "Net-(IC10-I5)") (class "Default")
      (node (ref "IC10") (pin "5") (pinfunction "I5_5") (pintype "input"))
      (node (ref "IC5") (pin "3") (pinfunction "QD_3") (pintype "tri_state"))
    )
    (net (code "61") (name "Net-(IC10-I6)") (class "Default")
      (node (ref "IC10") (pin "6") (pinfunction "I6_6") (pintype "input"))
      (node (ref "IC5") (pin "2") (pinfunction "QC_2") (pintype "tri_state"))
    )
    (net (code "62") (name "Net-(IC10-I7)") (class "Default")
      (node (ref "IC10") (pin "7") (pinfunction "I7_7") (pintype "input"))
      (node (ref "IC5") (pin "1") (pinfunction "QB_1") (pintype "tri_state"))
    )
    (net (code "63") (name "Net-(IC10-I8)") (class "Default")
      (node (ref "IC10") (pin "8") (pinfunction "I8_8") (pintype "input"))
      (node (ref "IC5") (pin "15") (pinfunction "QA_15") (pintype "tri_state"))
    )
    (net (code "64") (name "SEG1") (class "Default")
      (node (ref "IC6") (pin "11") (pinfunction "O8_11") (pintype "open_collector"))
      (node (ref "LED1") (pin "8") (pinfunction "COM_8") (pintype "passive"))
    )
    (net (code "65") (name "SEG2") (class "Default")
      (node (ref "IC6") (pin "12") (pinfunction "O7_12") (pintype "open_collector"))
      (node (ref "LED2") (pin "8") (pinfunction "COM_8") (pintype "passive"))
    )
    (net (code "66") (name "SEG3") (class "Default")
      (node (ref "IC6") (pin "13") (pinfunction "O6_13") (pintype "open_collector"))
      (node (ref "LED3") (pin "8") (pinfunction "COM_8") (pintype "passive"))
    )
    (net (code "67") (name "SEG4") (class "Default")
      (node (ref "IC6") (pin "14") (pinfunction "O5_14") (pintype "open_collector"))
      (node (ref "LED4") (pin "8") (pinfunction "COM_8") (pintype "passive"))
    )
    (net (code "68") (name "SEG5") (class "Default")
      (node (ref "IC6") (pin "15") (pinfunction "O4_15") (pintype "open_collector"))
      (node (ref "LED5") (pin "8") (pinfunction "COM_8") (pintype "passive"))
    )
    (net (code "69") (name "SEG6") (class "Default")
      (node (ref "IC6") (pin "16") (pinfunction "O3_16") (pintype "open_collector"))
      (node (ref "LED6") (pin "8") (pinfunction "COM_8") (pintype "passive"))
    )
    (net (code "70") (name "SEG7") (class "Default")
      (node (ref "IC6") (pin "17") (pinfunction "O2_17") (pintype "open_collector"))
      (node (ref "LED7") (pin "8") (pinfunction "COM_8") (pintype "passive"))
    )
    (net (code "71") (name "SEG8") (class "Default")
      (node (ref "IC6") (pin "18") (pinfunction "O1_18") (pintype "open_collector"))
      (node (ref "LED8") (pin "8") (pinfunction "COM_8") (pintype "passive"))
    )
    (net (code "72") (name "SEG9") (class "Default")
      (node (ref "IC7") (pin "11") (pinfunction "O8_11") (pintype "open_collector"))
      (node (ref "LED9") (pin "8") (pinfunction "COM_8") (pintype "passive"))
    )
    (net (code "73") (name "SEG10") (class "Default")
      (node (ref "IC7") (pin "12") (pinfunction "O7_12") (pintype "open_collector"))
      (node (ref "LED10") (pin "8") (pinfunction "COM_8") (pintype "passive"))
    )
    (net (code "74") (name "SEG11") (class "Default")
      (node (ref "IC7") (pin "13") (pinfunction "O6_13") (pintype "open_collector"))
      (node (ref "LED11") (pin "8") (pinfunction "COM_8") (pintype "passive"))
    )
    (net (code "75") (name "SEG12") (class "Default")
      (node (ref "IC7") (pin "14") (pinfunction "O5_14") (pintype "open_collector"))
      (node (ref "LED12") (pin "8") (pinfunction "COM_8") (pintype "passive"))
    )
    (net (code "76") (name "SEG13") (class "Default")
      (node (ref "IC7") (pin "15") (pinfunction "O4_15") (pintype "open_collector"))
      (node (ref "LED13") (pin "8") (pinfunction "COM_8") (pintype "passive"))
    )
    (net (code "77") (name "SEG14") (class "Default")
      (node (ref "IC7") (pin "16") (pinfunction "O3_16") (pintype "open_collector"))
      (node (ref "LED14") (pin "8") (pinfunction "COM_8") (pintype "passive"))
    )
    (net (code "78") (name "SEG15") (class "Default")
      (node (ref "IC7") (pin "17") (pinfunction "O2_17") (pintype "open_collector"))
      (node (ref "LED15") (pin "8") (pinfunction "COM_8") (pintype "passive"))
    )
    (net (code "79") (name "SEG16") (class "Default")
      (node (ref "IC7") (pin "18") (pinfunction "O1_18") (pintype "open_collector"))
      (node (ref "LED16") (pin "8") (pinfunction "COM_8") (pintype "passive"))
    )
    (net (code "80") (name "SEG17") (class "Default")
      (node (ref "IC8") (pin "11") (pinfunction "O8_11") (pintype "open_collector"))
      (node (ref "LED17") (pin "8") (pinfunction "COM_8") (pintype "passive"))
    )
    (net (code "81") (name "SEG18") (class "Default")
      (node (ref "IC8") (pin "12") (pinfunction "O7_12") (pintype "open_collector"))
      (node (ref "LED18") (pin "8") (pinfunction "COM_8") (pintype "passive"))
    )
    (net (code "82") (name "SEG19") (class "Default")
      (node (ref "IC8") (pin "13") (pinfunction "O6_13") (pintype "open_collector"))
      (node (ref "LED19") (pin "8") (pinfunction "COM_8") (pintype "passive"))
    )
    (net (code "83") (name "SEG20") (class "Default")
      (node (ref "IC8") (pin "14") (pinfunction "O5_14") (pintype "open_collector"))
      (node (ref "LED20") (pin "8") (pinfunction "COM_8") (pintype "passive"))
    )
    (net (code "84") (name "SEG21") (class "Default")
      (node (ref "IC8") (pin "15") (pinfunction "O4_15") (pintype "open_collector"))
      (node (ref "LED21") (pin "8") (pinfunction "COM_8") (pintype "passive"))
    )
    (net (code "85") (name "SEG22") (class "Default")
      (node (ref "IC8") (pin "16") (pinfunction "O3_16") (pintype "open_collector"))
      (node (ref "LED22") (pin "8") (pinfunction "COM_8") (pintype "passive"))
    )
    (net (code "86") (name "SEG23") (class "Default")
      (node (ref "IC8") (pin "17") (pinfunction "O2_17") (pintype "open_collector"))
      (node (ref "LED23") (pin "8") (pinfunction "COM_8") (pintype "passive"))
    )
    (net (code "87") (name "SEG24") (class "Default")
      (node (ref "IC8") (pin "18") (pinfunction "O1_18") (pintype "open_collector"))
      (node (ref "LED24") (pin "8") (pinfunction "COM_8") (pintype "passive"))
    )
    (net (code "88") (name "SEG25") (class "Default")
      (node (ref "IC9") (pin "11") (pinfunction "O8_11") (pintype "open_collector"))
      (node (ref "LED25") (pin "8") (pinfunction "COM_8") (pintype "passive"))
    )
    (net (code "89") (name "SEG26") (class "Default")
      (node (ref "IC9") (pin "12") (pinfunction "O7_12") (pintype "open_collector"))
      (node (ref "LED26") (pin "8") (pinfunction "COM_8") (pintype "passive"))
    )
    (net (code "90") (name "SEG27") (class "Default")
      (node (ref "IC9") (pin "13") (pinfunction "O6_13") (pintype "open_collector"))
      (node (ref "LED27") (pin "8") (pinfunction "COM_8") (pintype "passive"))
    )
    (net (code "91") (name "SEG28") (class "Default")
      (node (ref "IC9") (pin "14") (pinfunction "O5_14") (pintype "open_collector"))
      (node (ref "LED28") (pin "8") (pinfunction "COM_8") (pintype "passive"))
    )
    (net (code "92") (name "SEG29") (class "Default")
      (node (ref "IC9") (pin "15") (pinfunction "O4_15") (pintype "open_collector"))
      (node (ref "LED29") (pin "8") (pinfunction "COM_8") (pintype "passive"))
    )
    (net (code "93") (name "SEG30") (class "Default")
      (node (ref "IC9") (pin "16") (pinfunction "O3_16") (pintype "open_collector"))
      (node (ref "LED30") (pin "8") (pinfunction "COM_8") (pintype "passive"))
    )
    (net (code "94") (name "SEG31") (class "Default")
      (node (ref "IC9") (pin "17") (pinfunction "O2_17") (pintype "open_collector"))
      (node (ref "LED31") (pin "8") (pinfunction "COM_8") (pintype "passive"))
    )
    (net (code "95") (name "SEG32") (class "Default")
      (node (ref "IC9") (pin "18") (pinfunction "O1_18") (pintype "open_collector"))
      (node (ref "LED32") (pin "8") (pinfunction "COM_8") (pintype "passive"))
    )
    (net (code "96") (name "SEG33") (class "Default")
      (node (ref "IC10") (pin "11") (pinfunction "O8_11") (pintype "open_collector"))
      (node (ref "LED33") (pin "8") (pinfunction "COM_8") (pintype "passive"))
    )
    (net (code "97") (name "SEG34") (class "Default")
      (node (ref "IC10") (pin "12") (pinfunction "O7_12") (pintype "open_collector"))
      (node (ref "LED34") (pin "8") (pinfunction "COM_8") (pintype "passive"))
    )
    (net (code "98") (name "SEG35") (class "Default")
      (node (ref "IC10") (pin "13") (pinfunction "O6_13") (pintype "open_collector"))
      (node (ref "LED35") (pin "8") (pinfunction "COM_8") (pintype "passive"))
    )
    (net (code "99") (name "SEG36") (class "Default")
      (node (ref "IC10") (pin "14") (pinfunction "O5_14") (pintype "open_collector"))
      (node (ref "LED36") (pin "8") (pinfunction "COM_8") (pintype "passive"))
    )
    (net (code "100") (name "SEG37") (class "Default")
      (node (ref "IC10") (pin "15") (pinfunction "O4_15") (pintype "open_collector"))
      (node (ref "LED37") (pin "8") (pinfunction "COM_8") (pintype "passive"))
    )
    (net (code "101") (name "SEG38") (class "Default")
      (node (ref "IC10") (pin "16") (pinfunction "O3_16") (pintype "open_collector"))
      (node (ref "LED38") (pin "8") (pinfunction "COM_8") (pintype "passive"))
    )
    (net (code "102") (name "SEG39") (class "Default")
      (node (ref "IC10") (pin "17") (pinfunction "O2_17") (pintype "open_collector"))
      (node (ref "LED39") (pin "8") (pinfunction "COM_8") (pintype "passive"))
    )
    (net (code "103") (name "SEG40") (class "Default")
      (node (ref "IC10") (pin "18") (pinfunction "O1_18") (pintype "open_collector"))
      (node (ref "LED40") (pin "8") (pinfunction "COM_8") (pintype "passive"))
    )
    (net (code "104") (name "SH_CP") (class "Default")
      (node (ref "IC1") (pin "11") (pinfunction "SCK_11") (pintype "input"))
      (node (ref "IC2") (pin "11") (pinfunction "SCK_11") (pintype "input"))
      (node (ref "IC3") (pin "11") (pinfunction "SCK_11") (pintype "input"))
      (node (ref "IC4") (pin "11") (pinfunction "SCK_11") (pintype "input"))
      (node (ref "IC5") (pin "11") (pinfunction "SCK_11") (pintype "input"))
    )
    (net (code "105") (name "ST_CP") (class "Default")
      (node (ref "IC1") (pin "12") (pinfunction "RCK_12") (pintype "input"))
      (node (ref "IC2") (pin "12") (pinfunction "RCK_12") (pintype "input"))
      (node (ref "IC3") (pin "12") (pinfunction "RCK_12") (pintype "input"))
      (node (ref "IC4") (pin "12") (pinfunction "RCK_12") (pintype "input"))
      (node (ref "IC5") (pin "12") (pinfunction "RCK_12") (pintype "input"))
    )
    (net (code "106") (name "VCC") (class "Default")
      (node (ref "IC1") (pin "16") (pinfunction "VCC_16") (pintype "power_in"))
      (node (ref "IC10") (pin "10") (pinfunction "CD+_10") (pintype "passive"))
      (node (ref "IC2") (pin "16") (pinfunction "VCC_16") (pintype "power_in"))
      (node (ref "IC3") (pin "16") (pinfunction "VCC_16") (pintype "power_in"))
      (node (ref "IC4") (pin "16") (pinfunction "VCC_16") (pintype "power_in"))
      (node (ref "IC5") (pin "16") (pinfunction "VCC_16") (pintype "power_in"))
      (node (ref "IC6") (pin "10") (pinfunction "CD+_10") (pintype "passive"))
      (node (ref "IC7") (pin "10") (pinfunction "CD+_10") (pintype "passive"))
      (node (ref "IC8") (pin "10") (pinfunction "CD+_10") (pintype "passive"))
      (node (ref "IC9") (pin "10") (pinfunction "CD+_10") (pintype "passive"))
      (node (ref "T1") (pin "3") (pinfunction "C_3") (pintype "passive"))
      (node (ref "T2") (pin "3") (pinfunction "C_3") (pintype "passive"))
      (node (ref "T3") (pin "3") (pinfunction "C_3") (pintype "passive"))
      (node (ref "T4") (pin "3") (pinfunction "C_3") (pintype "passive"))
      (node (ref "T5") (pin "3") (pinfunction "C_3") (pintype "passive"))
      (node (ref "T6") (pin "3") (pinfunction "C_3") (pintype "passive"))
      (node (ref "T7") (pin "3") (pinfunction "C_3") (pintype "passive"))
      (node (ref "T8") (pin "3") (pinfunction "C_3") (pintype "passive"))
    )
    (net (code "107") (name "unconnected-(IC5A-QH*-Pad9)") (class "Default")
      (node (ref "IC5") (pin "9") (pinfunction "QH*_9") (pintype "tri_state"))
    )
    (net (code "108") (name "unconnected-(LED1-COM-Pad3)") (class "Default")
      (node (ref "LED1") (pin "3") (pinfunction "COM_3") (pintype "passive"))
    )
    (net (code "109") (name "unconnected-(LED2-COM-Pad3)") (class "Default")
      (node (ref "LED2") (pin "3") (pinfunction "COM_3") (pintype "passive"))
    )
    (net (code "110") (name "unconnected-(LED3-COM-Pad3)") (class "Default")
      (node (ref "LED3") (pin "3") (pinfunction "COM_3") (pintype "passive"))
    )
    (net (code "111") (name "unconnected-(LED4-COM-Pad3)") (class "Default")
      (node (ref "LED4") (pin "3") (pinfunction "COM_3") (pintype "passive"))
    )
    (net (code "112") (name "unconnected-(LED5-COM-Pad3)") (class "Default")
      (node (ref "LED5") (pin "3") (pinfunction "COM_3") (pintype "passive"))
    )
    (net (code "113") (name "unconnected-(LED6-COM-Pad3)") (class "Default")
      (node (ref "LED6") (pin "3") (pinfunction "COM_3") (pintype "passive"))
    )
    (net (code "114") (name "unconnected-(LED7-COM-Pad3)") (class "Default")
      (node (ref "LED7") (pin "3") (pinfunction "COM_3") (pintype "passive"))
    )
    (net (code "115") (name "unconnected-(LED8-COM-Pad3)") (class "Default")
      (node (ref "LED8") (pin "3") (pinfunction "COM_3") (pintype "passive"))
    )
    (net (code "116") (name "unconnected-(LED9-COM-Pad3)") (class "Default")
      (node (ref "LED9") (pin "3") (pinfunction "COM_3") (pintype "passive"))
    )
    (net (code "117") (name "unconnected-(LED10-COM-Pad3)") (class "Default")
      (node (ref "LED10") (pin "3") (pinfunction "COM_3") (pintype "passive"))
    )
    (net (code "118") (name "unconnected-(LED11-COM-Pad3)") (class "Default")
      (node (ref "LED11") (pin "3") (pinfunction "COM_3") (pintype "passive"))
    )
    (net (code "119") (name "unconnected-(LED12-COM-Pad3)") (class "Default")
      (node (ref "LED12") (pin "3") (pinfunction "COM_3") (pintype "passive"))
    )
    (net (code "120") (name "unconnected-(LED13-COM-Pad3)") (class "Default")
      (node (ref "LED13") (pin "3") (pinfunction "COM_3") (pintype "passive"))
    )
    (net (code "121") (name "unconnected-(LED14-COM-Pad3)") (class "Default")
      (node (ref "LED14") (pin "3") (pinfunction "COM_3") (pintype "passive"))
    )
    (net (code "122") (name "unconnected-(LED15-COM-Pad3)") (class "Default")
      (node (ref "LED15") (pin "3") (pinfunction "COM_3") (pintype "passive"))
    )
    (net (code "123") (name "unconnected-(LED16-COM-Pad3)") (class "Default")
      (node (ref "LED16") (pin "3") (pinfunction "COM_3") (pintype "passive"))
    )
    (net (code "124") (name "unconnected-(LED17-COM-Pad3)") (class "Default")
      (node (ref "LED17") (pin "3") (pinfunction "COM_3") (pintype "passive"))
    )
    (net (code "125") (name "unconnected-(LED18-COM-Pad3)") (class "Default")
      (node (ref "LED18") (pin "3") (pinfunction "COM_3") (pintype "passive"))
    )
    (net (code "126") (name "unconnected-(LED19-COM-Pad3)") (class "Default")
      (node (ref "LED19") (pin "3") (pinfunction "COM_3") (pintype "passive"))
    )
    (net (code "127") (name "unconnected-(LED20-COM-Pad3)") (class "Default")
      (node (ref "LED20") (pin "3") (pinfunction "COM_3") (pintype "passive"))
    )
    (net (code "128") (name "unconnected-(LED21-COM-Pad3)") (class "Default")
      (node (ref "LED21") (pin "3") (pinfunction "COM_3") (pintype "passive"))
    )
    (net (code "129") (name "unconnected-(LED22-COM-Pad3)") (class "Default")
      (node (ref "LED22") (pin "3") (pinfunction "COM_3") (pintype "passive"))
    )
    (net (code "130") (name "unconnected-(LED23-COM-Pad3)") (class "Default")
      (node (ref "LED23") (pin "3") (pinfunction "COM_3") (pintype "passive"))
    )
    (net (code "131") (name "unconnected-(LED24-COM-Pad3)") (class "Default")
      (node (ref "LED24") (pin "3") (pinfunction "COM_3") (pintype "passive"))
    )
    (net (code "132") (name "unconnected-(LED25-COM-Pad3)") (class "Default")
      (node (ref "LED25") (pin "3") (pinfunction "COM_3") (pintype "passive"))
    )
    (net (code "133") (name "unconnected-(LED26-COM-Pad3)") (class "Default")
      (node (ref "LED26") (pin "3") (pinfunction "COM_3") (pintype "passive"))
    )
    (net (code "134") (name "unconnected-(LED27-COM-Pad3)") (class "Default")
      (node (ref "LED27") (pin "3") (pinfunction "COM_3") (pintype "passive"))
    )
    (net (code "135") (name "unconnected-(LED28-COM-Pad3)") (class "Default")
      (node (ref "LED28") (pin "3") (pinfunction "COM_3") (pintype "passive"))
    )
    (net (code "136") (name "unconnected-(LED29-COM-Pad3)") (class "Default")
      (node (ref "LED29") (pin "3") (pinfunction "COM_3") (pintype "passive"))
    )
    (net (code "137") (name "unconnected-(LED30-COM-Pad3)") (class "Default")
      (node (ref "LED30") (pin "3") (pinfunction "COM_3") (pintype "passive"))
    )
    (net (code "138") (name "unconnected-(LED31-COM-Pad3)") (class "Default")
      (node (ref "LED31") (pin "3") (pinfunction "COM_3") (pintype "passive"))
    )
    (net (code "139") (name "unconnected-(LED32-COM-Pad3)") (class "Default")
      (node (ref "LED32") (pin "3") (pinfunction "COM_3") (pintype "passive"))
    )
    (net (code "140") (name "unconnected-(LED33-COM-Pad3)") (class "Default")
      (node (ref "LED33") (pin "3") (pinfunction "COM_3") (pintype "passive"))
    )
    (net (code "141") (name "unconnected-(LED34-COM-Pad3)") (class "Default")
      (node (ref "LED34") (pin "3") (pinfunction "COM_3") (pintype "passive"))
    )
    (net (code "142") (name "unconnected-(LED35-COM-Pad3)") (class "Default")
      (node (ref "LED35") (pin "3") (pinfunction "COM_3") (pintype "passive"))
    )
    (net (code "143") (name "unconnected-(LED36-COM-Pad3)") (class "Default")
      (node (ref "LED36") (pin "3") (pinfunction "COM_3") (pintype "passive"))
    )
    (net (code "144") (name "unconnected-(LED37-COM-Pad3)") (class "Default")
      (node (ref "LED37") (pin "3") (pinfunction "COM_3") (pintype "passive"))
    )
    (net (code "145") (name "unconnected-(LED38-COM-Pad3)") (class "Default")
      (node (ref "LED38") (pin "3") (pinfunction "COM_3") (pintype "passive"))
    )
    (net (code "146") (name "unconnected-(LED39-COM-Pad3)") (class "Default")
      (node (ref "LED39") (pin "3") (pinfunction "COM_3") (pintype "passive"))
    )
    (net (code "147") (name "unconnected-(LED40-COM-Pad3)") (class "Default")
      (node (ref "LED40") (pin "3") (pinfunction "COM_3") (pintype "passive"))
    )
  )
)
